# 3__schdoc.net
KiCad netlist of a schematic drawn in Altium Designer
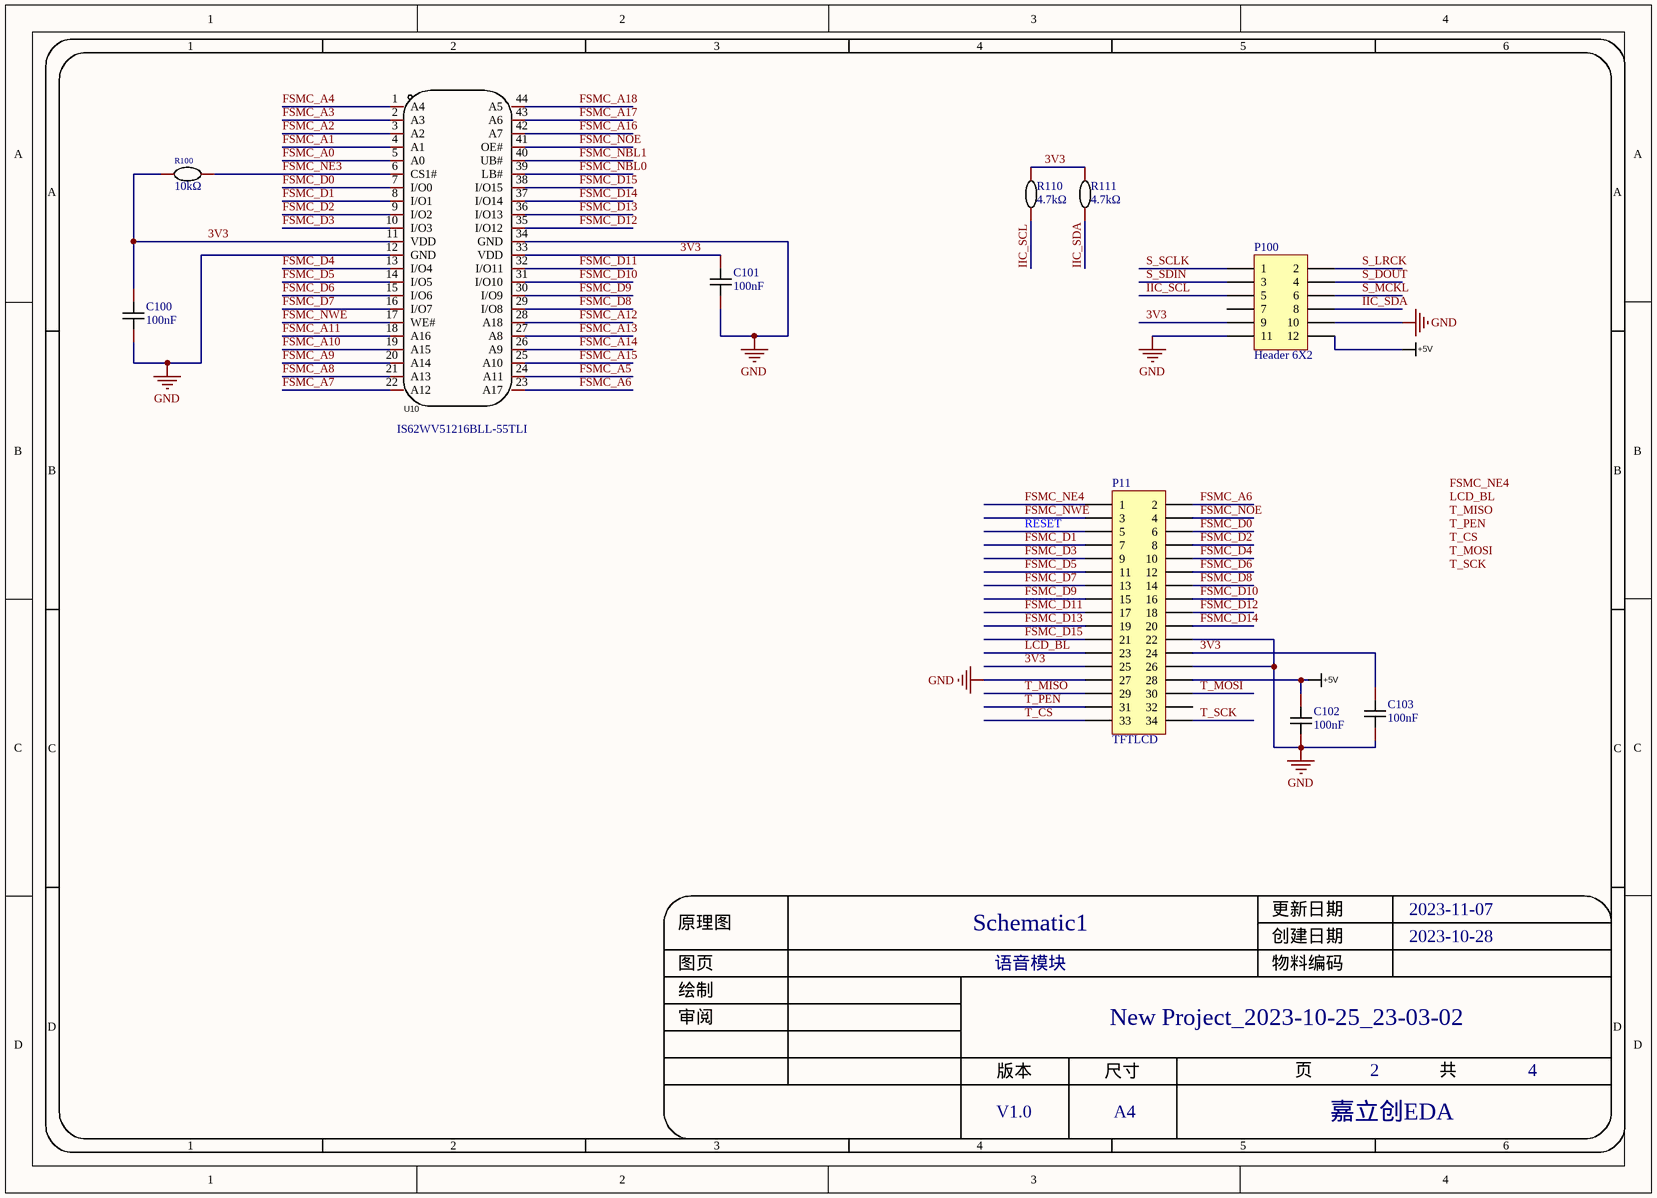
[diagram p0: 3_语音模块.schdoc.schdoc]

(export (version "E")
  (design (tool "Eeschema 10.0.6"))
  (components
    (comp (ref "C100")
      (value "100nF")
      (footprint "C0603")
      (description "容值:100nF;精度:±20%;额定电压:50V;材质(温度系数):X8R;")
      (fields
        (field (name "MANUFACTURER") "TDK")
        (field (name "MANUFACTURER PART") "CGA3E3X8R1H104M080AE")
        (field (name "NAME") "100nF")
      )
      (libsource (lib "int_lock") (part "CGA3E3X8R1H104M080AE"))
    )
    (comp (ref "C101")
      (value "100nF")
      (footprint "C0603")
      (description "容值:100nF;精度:±20%;额定电压:50V;材质(温度系数):X8R;")
      (fields
        (field (name "MANUFACTURER") "TDK")
        (field (name "MANUFACTURER PART") "CGA3E3X8R1H104M080AE")
        (field (name "NAME") "100nF")
      )
      (libsource (lib "int_lock") (part "CGA3E3X8R1H104M080AE"))
    )
    (comp (ref "C102")
      (value "100nF")
      (footprint "C0603")
      (description "容值:100nF;精度:±20%;额定电压:50V;材质(温度系数):X8R;")
      (fields
        (field (name "MANUFACTURER") "TDK")
        (field (name "MANUFACTURER PART") "CGA3E3X8R1H104M080AE")
        (field (name "NAME") "100nF")
      )
      (libsource (lib "int_lock") (part "CGA3E3X8R1H104M080AE"))
    )
    (comp (ref "C103")
      (value "100nF")
      (footprint "C0603")
      (description "容值:100nF;精度:±20%;额定电压:50V;材质(温度系数):X8R;")
      (fields
        (field (name "MANUFACTURER") "TDK")
        (field (name "MANUFACTURER PART") "CGA3E3X8R1H104M080AE")
        (field (name "NAME") "100nF")
      )
      (libsource (lib "int_lock") (part "CGA3E3X8R1H104M080AE"))
    )
    (comp (ref "P11")
      (value "TFTLCD")
      (footprint "HDR2X17")
      (description "Header, 17-Pin, Dual row")
      (fields (field (name "PUBLISHER") "Altium Limited"))
      (libsource (lib "Miscellaneous Connectors") (part "Header 17X2"))
    )
    (comp (ref "P100")
      (value "Header 6X2")
      (footprint "HDR2X6")
      (description "Header, 6-Pin, Dual row")
      (fields (field (name "PUBLISHER") "Altium Limited"))
      (libsource (lib "Miscellaneous Connectors") (part "Header 6X2"))
    )
    (comp (ref "R100")
      (value "10kΩ")
      (footprint "R0603")
      (description "阻值:10kΩ;精度:±5%;")
      (fields
        (field (name "NAME") "10kΩ")
        (field (name "MANUFACTURER") "VO(翔胜)")
        (field (name "MANUFACTURER PART") "SCR0603J10K")
      )
      (libsource (lib "int_lock") (part "SCR0603J10K"))
    )
    (comp (ref "R110")
      (value "4.7kΩ")
      (footprint "R0603")
      (description "电阻类型:薄膜电阻;阻值:4.7kΩ;精度:±1%;功率:100mW;")
      (fields
        (field (name "NAME") "4.7kΩ")
        (field (name "MANUFACTURER") "Viking(光颉)")
        (field (name "MANUFACTURER PART") "AR03FTDX4701A")
      )
      (libsource (lib "int_lock") (part "AR03FTDX4701A"))
    )
    (comp (ref "R111")
      (value "4.7kΩ")
      (footprint "R0603")
      (description "电阻类型:薄膜电阻;阻值:4.7kΩ;精度:±1%;功率:100mW;")
      (fields
        (field (name "NAME") "4.7kΩ")
        (field (name "MANUFACTURER") "Viking(光颉)")
        (field (name "MANUFACTURER PART") "AR03FTDX4701A")
      )
      (libsource (lib "int_lock") (part "AR03FTDX4701A"))
    )
    (comp (ref "U10")
      (value "IS62WV51216BLL-55TLI")
      (footprint "SRAM")
      (fields (field (name "MANUFACTURER") "ISSI(美国芯成)"))
      (libsource (lib "int_lock") (part "IS62WV51216BLL-55TLI"))
    )
  )
  (nets
    (net (code "1") (name "+5V") (class "Default")
      (node (ref "C102") (pin "2") (pinfunction "2_2") (pintype "passive"))
      (node (ref "P100") (pin "12") (pinfunction "12_12") (pintype "passive"))
      (node (ref "P11") (pin "28") (pinfunction "28_28") (pintype "passive"))
    )
    (net (code "2") (name "/3V3") (class "Default")
      (node (ref "C100") (pin "2") (pinfunction "2_2") (pintype "passive"))
      (node (ref "C101") (pin "2") (pinfunction "2_2") (pintype "passive"))
      (node (ref "C103") (pin "2") (pinfunction "2_2") (pintype "passive"))
      (node (ref "P100") (pin "9") (pinfunction "9_9") (pintype "passive"))
      (node (ref "P11") (pin "24") (pinfunction "24_24") (pintype "passive"))
      (node (ref "P11") (pin "25") (pinfunction "25_25") (pintype "passive"))
      (node (ref "R100") (pin "1") (pinfunction "1_1") (pintype "passive"))
      (node (ref "R110") (pin "2") (pinfunction "2_2") (pintype "passive"))
      (node (ref "R111") (pin "2") (pinfunction "2_2") (pintype "passive"))
      (node (ref "U10") (pin "11") (pinfunction "VDD_11") (pintype "passive"))
      (node (ref "U10") (pin "33") (pinfunction "VDD_33") (pintype "passive"))
    )
    (net (code "3") (name "/FSMC_A0") (class "Default")
      (node (ref "U10") (pin "5") (pinfunction "A0_5") (pintype "passive"))
    )
    (net (code "4") (name "/FSMC_A1") (class "Default")
      (node (ref "U10") (pin "4") (pinfunction "A1_4") (pintype "passive"))
    )
    (net (code "5") (name "/FSMC_A2") (class "Default")
      (node (ref "U10") (pin "3") (pinfunction "A2_3") (pintype "passive"))
    )
    (net (code "6") (name "/FSMC_A3") (class "Default")
      (node (ref "U10") (pin "2") (pinfunction "A3_2") (pintype "passive"))
    )
    (net (code "7") (name "/FSMC_A4") (class "Default")
      (node (ref "U10") (pin "1") (pinfunction "A4_1") (pintype "passive"))
    )
    (net (code "8") (name "/FSMC_A5") (class "Default")
      (node (ref "U10") (pin "24") (pinfunction "A11_24") (pintype "passive"))
    )
    (net (code "9") (name "/FSMC_A6") (class "Default")
      (node (ref "P11") (pin "2") (pinfunction "2_2") (pintype "passive"))
      (node (ref "U10") (pin "23") (pinfunction "A17_23") (pintype "passive"))
    )
    (net (code "10") (name "/FSMC_A7") (class "Default")
      (node (ref "U10") (pin "22") (pinfunction "A12_22") (pintype "passive"))
    )
    (net (code "11") (name "/FSMC_A8") (class "Default")
      (node (ref "U10") (pin "21") (pinfunction "A13_21") (pintype "passive"))
    )
    (net (code "12") (name "/FSMC_A9") (class "Default")
      (node (ref "U10") (pin "20") (pinfunction "A14_20") (pintype "passive"))
    )
    (net (code "13") (name "/FSMC_A10") (class "Default")
      (node (ref "U10") (pin "19") (pinfunction "A15_19") (pintype "passive"))
    )
    (net (code "14") (name "/FSMC_A11") (class "Default")
      (node (ref "U10") (pin "18") (pinfunction "A16_18") (pintype "passive"))
    )
    (net (code "15") (name "/FSMC_A12") (class "Default")
      (node (ref "U10") (pin "28") (pinfunction "A18_28") (pintype "passive"))
    )
    (net (code "16") (name "/FSMC_A13") (class "Default")
      (node (ref "U10") (pin "27") (pinfunction "A8_27") (pintype "passive"))
    )
    (net (code "17") (name "/FSMC_A14") (class "Default")
      (node (ref "U10") (pin "26") (pinfunction "A9_26") (pintype "passive"))
    )
    (net (code "18") (name "/FSMC_A15") (class "Default")
      (node (ref "U10") (pin "25") (pinfunction "A10_25") (pintype "passive"))
    )
    (net (code "19") (name "/FSMC_A16") (class "Default")
      (node (ref "U10") (pin "42") (pinfunction "A7_42") (pintype "passive"))
    )
    (net (code "20") (name "/FSMC_A17") (class "Default")
      (node (ref "U10") (pin "43") (pinfunction "A6_43") (pintype "passive"))
    )
    (net (code "21") (name "/FSMC_A18") (class "Default")
      (node (ref "U10") (pin "44") (pinfunction "A5_44") (pintype "passive"))
    )
    (net (code "22") (name "/FSMC_D0") (class "Default")
      (node (ref "P11") (pin "6") (pinfunction "6_6") (pintype "passive"))
      (node (ref "U10") (pin "7") (pinfunction "I/O0_7") (pintype "passive"))
    )
    (net (code "23") (name "/FSMC_D1") (class "Default")
      (node (ref "P11") (pin "7") (pinfunction "7_7") (pintype "passive"))
      (node (ref "U10") (pin "8") (pinfunction "I/O1_8") (pintype "passive"))
    )
    (net (code "24") (name "/FSMC_D2") (class "Default")
      (node (ref "P11") (pin "8") (pinfunction "8_8") (pintype "passive"))
      (node (ref "U10") (pin "9") (pinfunction "I/O2_9") (pintype "passive"))
    )
    (net (code "25") (name "/FSMC_D3") (class "Default")
      (node (ref "P11") (pin "9") (pinfunction "9_9") (pintype "passive"))
      (node (ref "U10") (pin "10") (pinfunction "I/O3_10") (pintype "passive"))
    )
    (net (code "26") (name "/FSMC_D4") (class "Default")
      (node (ref "P11") (pin "10") (pinfunction "10_10") (pintype "passive"))
      (node (ref "U10") (pin "13") (pinfunction "I/O4_13") (pintype "passive"))
    )
    (net (code "27") (name "/FSMC_D5") (class "Default")
      (node (ref "P11") (pin "11") (pinfunction "11_11") (pintype "passive"))
      (node (ref "U10") (pin "14") (pinfunction "I/O5_14") (pintype "passive"))
    )
    (net (code "28") (name "/FSMC_D6") (class "Default")
      (node (ref "P11") (pin "12") (pinfunction "12_12") (pintype "passive"))
      (node (ref "U10") (pin "15") (pinfunction "I/O6_15") (pintype "passive"))
    )
    (net (code "29") (name "/FSMC_D7") (class "Default")
      (node (ref "P11") (pin "13") (pinfunction "13_13") (pintype "passive"))
      (node (ref "U10") (pin "16") (pinfunction "I/O7_16") (pintype "passive"))
    )
    (net (code "30") (name "/FSMC_D8") (class "Default")
      (node (ref "P11") (pin "14") (pinfunction "14_14") (pintype "passive"))
      (node (ref "U10") (pin "29") (pinfunction "I/O8_29") (pintype "passive"))
    )
    (net (code "31") (name "/FSMC_D9") (class "Default")
      (node (ref "P11") (pin "15") (pinfunction "15_15") (pintype "passive"))
      (node (ref "U10") (pin "30") (pinfunction "I/O9_30") (pintype "passive"))
    )
    (net (code "32") (name "/FSMC_D10") (class "Default")
      (node (ref "P11") (pin "16") (pinfunction "16_16") (pintype "passive"))
      (node (ref "U10") (pin "31") (pinfunction "I/O10_31") (pintype "passive"))
    )
    (net (code "33") (name "/FSMC_D11") (class "Default")
      (node (ref "P11") (pin "17") (pinfunction "17_17") (pintype "passive"))
      (node (ref "U10") (pin "32") (pinfunction "I/O11_32") (pintype "passive"))
    )
    (net (code "34") (name "/FSMC_D12") (class "Default")
      (node (ref "P11") (pin "18") (pinfunction "18_18") (pintype "passive"))
      (node (ref "U10") (pin "35") (pinfunction "I/O12_35") (pintype "passive"))
    )
    (net (code "35") (name "/FSMC_D13") (class "Default")
      (node (ref "P11") (pin "19") (pinfunction "19_19") (pintype "passive"))
      (node (ref "U10") (pin "36") (pinfunction "I/O13_36") (pintype "passive"))
    )
    (net (code "36") (name "/FSMC_D14") (class "Default")
      (node (ref "P11") (pin "20") (pinfunction "20_20") (pintype "passive"))
      (node (ref "U10") (pin "37") (pinfunction "I/O14_37") (pintype "passive"))
    )
    (net (code "37") (name "/FSMC_D15") (class "Default")
      (node (ref "P11") (pin "21") (pinfunction "21_21") (pintype "passive"))
      (node (ref "U10") (pin "38") (pinfunction "I/O15_38") (pintype "passive"))
    )
    (net (code "38") (name "/FSMC_NBL0") (class "Default")
      (node (ref "U10") (pin "39") (pinfunction "LB#_39") (pintype "passive"))
    )
    (net (code "39") (name "/FSMC_NBL1") (class "Default")
      (node (ref "U10") (pin "40") (pinfunction "UB#_40") (pintype "passive"))
    )
    (net (code "40") (name "/FSMC_NE3") (class "Default")
      (node (ref "R100") (pin "2") (pinfunction "2_2") (pintype "passive"))
      (node (ref "U10") (pin "6") (pinfunction "CS1#_6") (pintype "passive"))
    )
    (net (code "41") (name "/FSMC_NE4") (class "Default")
      (node (ref "P11") (pin "1") (pinfunction "1_1") (pintype "passive"))
    )
    (net (code "42") (name "/FSMC_NOE") (class "Default")
      (node (ref "P11") (pin "4") (pinfunction "4_4") (pintype "passive"))
      (node (ref "U10") (pin "41") (pinfunction "OE#_41") (pintype "passive"))
    )
    (net (code "43") (name "/FSMC_NWE") (class "Default")
      (node (ref "P11") (pin "3") (pinfunction "3_3") (pintype "passive"))
      (node (ref "U10") (pin "17") (pinfunction "WE#_17") (pintype "passive"))
    )
    (net (code "44") (name "/IIC_SCL") (class "Default")
      (node (ref "P100") (pin "5") (pinfunction "5_5") (pintype "passive"))
      (node (ref "R110") (pin "1") (pinfunction "1_1") (pintype "passive"))
    )
    (net (code "45") (name "/IIC_SDA") (class "Default")
      (node (ref "P100") (pin "8") (pinfunction "8_8") (pintype "passive"))
      (node (ref "R111") (pin "1") (pinfunction "1_1") (pintype "passive"))
    )
    (net (code "46") (name "/LCD_BL") (class "Default")
      (node (ref "P11") (pin "23") (pinfunction "23_23") (pintype "passive"))
    )
    (net (code "47") (name "/RESET") (class "Default")
      (node (ref "P11") (pin "5") (pinfunction "5_5") (pintype "passive"))
    )
    (net (code "48") (name "/S_DOUT") (class "Default")
      (node (ref "P100") (pin "4") (pinfunction "4_4") (pintype "passive"))
    )
    (net (code "49") (name "/S_LRCK") (class "Default")
      (node (ref "P100") (pin "2") (pinfunction "2_2") (pintype "passive"))
    )
    (net (code "50") (name "/S_MCKL") (class "Default")
      (node (ref "P100") (pin "6") (pinfunction "6_6") (pintype "passive"))
    )
    (net (code "51") (name "/S_SCLK") (class "Default")
      (node (ref "P100") (pin "1") (pinfunction "1_1") (pintype "passive"))
    )
    (net (code "52") (name "/S_SDIN") (class "Default")
      (node (ref "P100") (pin "3") (pinfunction "3_3") (pintype "passive"))
    )
    (net (code "53") (name "/T_CS") (class "Default")
      (node (ref "P11") (pin "33") (pinfunction "33_33") (pintype "passive"))
    )
    (net (code "54") (name "/T_MISO") (class "Default")
      (node (ref "P11") (pin "29") (pinfunction "29_29") (pintype "passive"))
    )
    (net (code "55") (name "/T_MOSI") (class "Default")
      (node (ref "P11") (pin "30") (pinfunction "30_30") (pintype "passive"))
    )
    (net (code "56") (name "/T_PEN") (class "Default")
      (node (ref "P11") (pin "31") (pinfunction "31_31") (pintype "passive"))
    )
    (net (code "57") (name "/T_SCK") (class "Default")
      (node (ref "P11") (pin "34") (pinfunction "34_34") (pintype "passive"))
    )
    (net (code "58") (name "GND") (class "Default")
      (node (ref "C100") (pin "1") (pinfunction "1_1") (pintype "passive"))
      (node (ref "C101") (pin "1") (pinfunction "1_1") (pintype "passive"))
      (node (ref "C102") (pin "1") (pinfunction "1_1") (pintype "passive"))
      (node (ref "C103") (pin "1") (pinfunction "1_1") (pintype "passive"))
      (node (ref "P100") (pin "10") (pinfunction "10_10") (pintype "passive"))
      (node (ref "P100") (pin "11") (pinfunction "11_11") (pintype "passive"))
      (node (ref "P11") (pin "22") (pinfunction "22_22") (pintype "passive"))
      (node (ref "P11") (pin "26") (pinfunction "26_26") (pintype "passive"))
      (node (ref "P11") (pin "27") (pinfunction "27_27") (pintype "passive"))
      (node (ref "U10") (pin "12") (pinfunction "GND_12") (pintype "passive"))
      (node (ref "U10") (pin "34") (pinfunction "GND_34") (pintype "passive"))
    )
    (net (code "59") (name "unconnected-(P11-Pad32)") (class "Default")
      (node (ref "P11") (pin "32") (pinfunction "32_32") (pintype "passive"))
    )
    (net (code "60") (name "unconnected-(P100-Pad7)") (class "Default")
      (node (ref "P100") (pin "7") (pinfunction "7_7") (pintype "passive"))
    )
  )
)
